# SP26_FindingTitan_Digital_Circuitry_Prak.net
KiCad netlist of a schematic drawn in Altium Designer
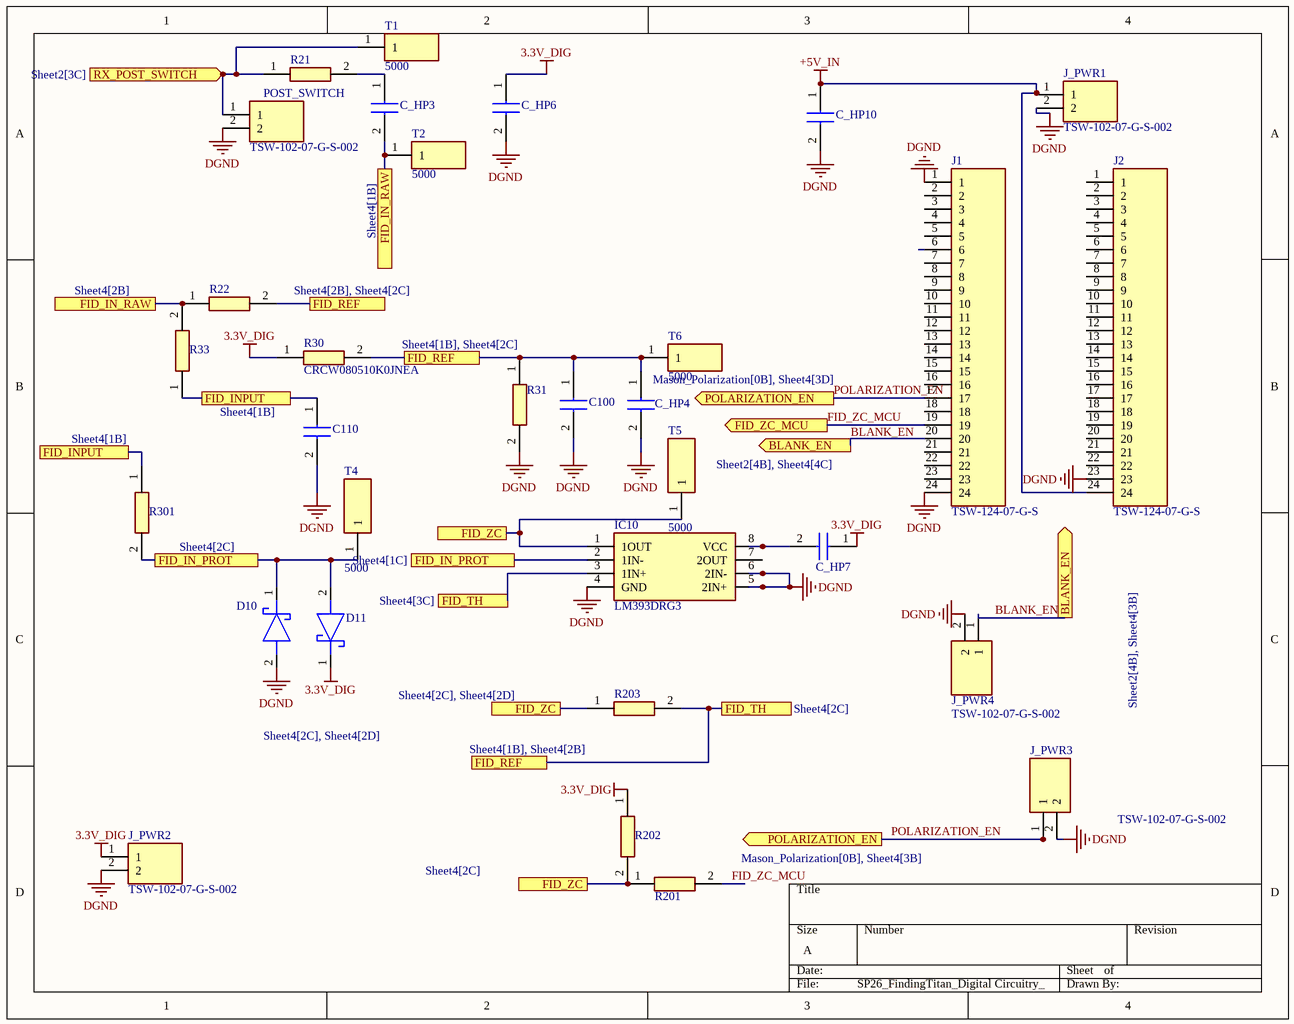
[diagram p0: SP26_FindingTitan_Digital Circuitry_Prakul Swaminath.SchDoc.SchDoc]

(export (version "E")
  (design (tool "Eeschema 10.0.6"))
  (components
    (comp (ref "C100")
      (value "C0805C105K5RACTU")
      (footprint "SamacSys:C0805")
      (description "Capacitor")
      (fields (field (name "MOUSER PART NUMBER") "80-C0805C105K5R"))
      (libsource (lib "*") (part "C0805C105K5RACTU"))
    )
    (comp (ref "C110")
      (value "GRM188R71H222KA01D")
      (footprint "SamacSys:CAPC1608X90N")
      (description "Capacitor")
      (fields (field (name "MOUSER PART NUMBER") "81-GRM39X222K50D"))
      (libsource (lib "*") (part "GRM188R71H222KA01D"))
    )
    (comp (ref "C_HP3")
      (value "C0603C104K5RACTU7042")
      (footprint "SamacSys:CAPC1608X95N")
      (description "Capacitor")
      (libsource (lib "*") (part "C0603C104K5RACTU7042"))
    )
    (comp (ref "C_HP4")
      (value "C0603C104K5RACTU7042C0603C104K5RACTU7042")
      (footprint "SamacSys:CAPC1608X95N")
      (description "Capacitor")
      (fields (field (name "MANUFACTURER_PART_NUMBER") "C0603C104K5RACTU7042"))
      (libsource (lib "*") (part "C0603C104K5RACTU7042"))
    )
    (comp (ref "C_HP6")
      (value "C0603C104K5RACTU7042C0603C104K5RACTU7042")
      (footprint "SamacSys:CAPC1608X95N")
      (description "Capacitor")
      (fields (field (name "MANUFACTURER_PART_NUMBER") "C0603C104K5RACTU7042"))
      (libsource (lib "*") (part "C0603C104K5RACTU7042"))
    )
    (comp (ref "C_HP7")
      (value "C0603C104K5RACTU7042C0603C104K5RACTU7042")
      (footprint "SamacSys:CAPC1608X95N")
      (description "Capacitor")
      (fields (field (name "MANUFACTURER_PART_NUMBER") "C0603C104K5RACTU7042"))
      (libsource (lib "*") (part "C0603C104K5RACTU7042"))
    )
    (comp (ref "C_HP10")
      (value "C0603C104K5RACTU7042C0603C104K5RACTU7042")
      (footprint "SamacSys:CAPC1608X95N")
      (description "Capacitor")
      (fields (field (name "MANUFACTURER_PART_NUMBER") "C0603C104K5RACTU7042"))
      (libsource (lib "*") (part "C0603C104K5RACTU7042"))
    )
    (comp (ref "D10")
      (value "BAT54HT1G")
      (footprint "SamacSys:SOD2512X110N")
      (description "Schottky Diode")
      (fields (field (name "MOUSER PART NUMBER") "863-BAT54HT1G"))
      (libsource (lib "*") (part "BAT54HT1G"))
    )
    (comp (ref "D11")
      (value "BAT54HT1G")
      (footprint "SamacSys:SOD2512X110N")
      (description "Schottky Diode")
      (fields (field (name "MOUSER PART NUMBER") "863-BAT54HT1G"))
      (libsource (lib "*") (part "BAT54HT1G"))
    )
    (comp (ref "IC10")
      (value "LM393DRG3")
      (footprint "SamacSys:SOIC127P600X175-8N")
      (description "Integrated Circuit")
      (fields (field (name "MOUSER PART NUMBER") "595-LM393DRG3"))
      (libsource (lib "*") (part "LM393DRG3"))
    )
    (comp (ref "J1")
      (value "TSW-124-07-G-S")
      (footprint "SamacSys:TSW-124-XX-YY-S")
      (description "Connector")
      (fields (field (name "MOUSER PART NUMBER") "200-TSW12407GS"))
      (libsource (lib "*") (part "TSW-124-07-G-S"))
    )
    (comp (ref "J2")
      (value "TSW-124-07-G-S")
      (footprint "SamacSys:TSW-124-XX-YY-S")
      (description "Connector")
      (fields (field (name "MOUSER PART NUMBER") "200-TSW12407GS"))
      (libsource (lib "*") (part "TSW-124-07-G-S"))
    )
    (comp (ref "J_PWR1")
      (value "TSW-102-07-G-S-002")
      (footprint "SamacSys:HDRV2W64P0X254_1X2_508X254X838P")
      (description "Connector")
      (fields (field (name "MOUSER PART NUMBER") "200-TSW-10207GS002"))
      (libsource (lib "*") (part "TSW-102-07-G-S-002"))
    )
    (comp (ref "J_PWR2")
      (value "TSW-102-07-G-S-002")
      (footprint "SamacSys:HDRV2W64P0X254_1X2_508X254X838P")
      (description "Connector")
      (fields (field (name "MOUSER PART NUMBER") "200-TSW-10207GS002"))
      (libsource (lib "*") (part "TSW-102-07-G-S-002"))
    )
    (comp (ref "J_PWR3")
      (value "TSW-102-07-G-S-002")
      (footprint "SamacSys:HDRV2W64P0X254_1X2_508X254X838P")
      (description "Connector")
      (fields (field (name "MOUSER PART NUMBER") "200-TSW-10207GS002"))
      (libsource (lib "") (part "TSW-102-07-G-S-002_2"))
    )
    (comp (ref "J_PWR4")
      (value "TSW-102-07-G-S-002")
      (footprint "SamacSys:HDRV2W64P0X254_1X2_508X254X838P")
      (description "Connector")
      (fields (field (name "MOUSER PART NUMBER") "200-TSW-10207GS002"))
      (libsource (lib "") (part "TSW-102-07-G-S-002_1"))
    )
    (comp (ref "POST_SWITCH")
      (value "TSW-102-07-G-S-002")
      (footprint "SamacSys:HDRV2W64P0X254_1X2_508X254X838P")
      (description "Connector")
      (fields (field (name "MOUSER PART NUMBER") "200-TSW-10207GS002"))
      (libsource (lib "*") (part "TSW-102-07-G-S-002"))
    )
    (comp (ref "R21")
      (value "RMCF0603FT1K00")
      (footprint "SamacSys:RESC1608X55N")
      (description "Resistor")
      (fields (field (name "MOUSER PART NUMBER") "708-RMCF0603FT1K00"))
      (libsource (lib "*") (part "RMCF0603FT1K00"))
    )
    (comp (ref "R22")
      (value "RC0805FR-07100KL")
      (footprint "SamacSys:RESC2012X60N")
      (description "Resistor")
      (fields (field (name "MOUSER PART NUMBER") "603-RC0805FR-07100KL"))
      (libsource (lib "*") (part "RC0805FR-07100KL"))
    )
    (comp (ref "R30")
      (value "CRCW080510K0JNEA")
      (footprint "SamacSys:RESC2012X50N")
      (description "Resistor")
      (fields (field (name "MOUSER PART NUMBER") "71-CRCW0805J-10K-E3"))
      (libsource (lib "") (part "CRCW080510K0JNEA_1"))
    )
    (comp (ref "R31")
      (value "CRCW080510K0JNEA")
      (footprint "SamacSys:RESC2012X50N")
      (description "Resistor")
      (fields (field (name "MOUSER PART NUMBER") "71-CRCW0805J-10K-E3"))
      (libsource (lib "*") (part "CRCW080510K0JNEA"))
    )
    (comp (ref "R33")
      (value "RC0402JR-074K7L")
      (footprint "SamacSys:RESC2012X60N")
      (description "Resistor")
      (fields
        (field (name "MANUFACTURER_PART_NUMBER") "RC0805FR-07100KL")
        (field (name "MOUSER PART NUMBER") "603-RC0805FR-07100KL")
      )
      (libsource (lib "") (part "RC0805FR-07100KL_1"))
    )
    (comp (ref "R201")
      (value "CRCW080547R0FKEA")
      (footprint "SamacSys:RESC2012X60N")
      (description "Resistor")
      (fields
        (field (name "MANUFACTURER_PART_NUMBER") "CRCW080510K0FKEAHP")
        (field (name "MOUSER PART NUMBER") "71-CRCW080510K0FKEAH")
      )
      (libsource (lib "*") (part "CRCW080510K0FKEAHP"))
    )
    (comp (ref "R202")
      (value "CRCW08054K70FKEA")
      (footprint "SamacSys:RESC2012X60N")
      (description "Resistor")
      (fields
        (field (name "MANUFACTURER_PART_NUMBER") "CRCW080510K0FKEAHP")
        (field (name "MOUSER PART NUMBER") "71-CRCW080510K0FKEAH")
      )
      (libsource (lib "") (part "CRCW080510K0FKEAHP_1"))
    )
    (comp (ref "R203")
      (value "CRCW08051M00FKEAHP")
      (footprint "SamacSys:RESC2012X60N")
      (description "Resistor")
      (fields (field (name "MOUSER PART NUMBER") "71-CRCW08051M00FKEAH"))
      (libsource (lib "*") (part "CRCW08051M00FKEAHP"))
    )
    (comp (ref "R301")
      (value "RC0805FR-07220RL")
      (footprint "SamacSys:RESC2012X60N")
      (description "Resistor")
      (fields (field (name "MOUSER PART NUMBER") "603-RC0805FR-07220RL"))
      (libsource (lib "*") (part "RC0805FR-07220RL"))
    )
    (comp (ref "T1")
      (value "5000")
      (footprint "SamacSys:5000")
      (description "Connector")
      (fields (field (name "MOUSER PART NUMBER") "534-5000"))
      (libsource (lib "") (part "5000_1"))
    )
    (comp (ref "T2")
      (value "5000")
      (footprint "SamacSys:5000")
      (description "Connector")
      (fields (field (name "MOUSER PART NUMBER") "534-5000"))
      (libsource (lib "") (part "5000_1"))
    )
    (comp (ref "T4")
      (value "5000")
      (footprint "SamacSys:5000")
      (description "Connector")
      (fields (field (name "MOUSER PART NUMBER") "534-5000"))
      (libsource (lib "*") (part "5000"))
    )
    (comp (ref "T5")
      (value "5000")
      (footprint "SamacSys:5000")
      (description "Connector")
      (fields (field (name "MOUSER PART NUMBER") "534-5000"))
      (libsource (lib "*") (part "5000"))
    )
    (comp (ref "T6")
      (value "5000")
      (footprint "SamacSys:5000")
      (description "Connector")
      (fields (field (name "MOUSER PART NUMBER") "534-5000"))
      (libsource (lib "") (part "5000_1"))
    )
  )
  (nets
    (net (code "1") (name "+5V_IN") (class "Default")
      (node (ref "C_HP10") (pin "1") (pinfunction "1_1") (pintype "passive"))
      (node (ref "J2") (pin "24") (pinfunction "24_24") (pintype "passive"))
      (node (ref "J_PWR1") (pin "1") (pinfunction "1_1") (pintype "passive"))
    )
    (net (code "3") (name "/BLANK_EN") (class "Default")
      (node (ref "J1") (pin "20") (pinfunction "20_20") (pintype "passive"))
      (node (ref "J_PWR4") (pin "1") (pinfunction "1_1") (pintype "passive"))
    )
    (net (code "4") (name "/FID_INPUT") (class "Default")
      (node (ref "C110") (pin "1") (pinfunction "1_1") (pintype "passive"))
      (node (ref "R301") (pin "1") (pinfunction "1_1") (pintype "passive"))
      (node (ref "R33") (pin "1") (pinfunction "1_1") (pintype "passive"))
    )
    (net (code "5") (name "/FID_IN_PROT") (class "Default")
      (node (ref "D10") (pin "1") (pinfunction "K_1") (pintype "passive"))
      (node (ref "D11") (pin "2") (pinfunction "A_2") (pintype "passive"))
      (node (ref "IC10") (pin "2") (pinfunction "1IN-_2") (pintype "passive"))
      (node (ref "R301") (pin "2") (pinfunction "2_2") (pintype "passive"))
      (node (ref "T4") (pin "1") (pinfunction "1_1") (pintype "passive"))
    )
    (net (code "6") (name "/FID_IN_RAW") (class "Default")
      (node (ref "C_HP3") (pin "2") (pinfunction "2_2") (pintype "passive"))
      (node (ref "R22") (pin "1") (pinfunction "1_1") (pintype "passive"))
      (node (ref "R33") (pin "2") (pinfunction "2_2") (pintype "passive"))
      (node (ref "T2") (pin "1") (pinfunction "1_1") (pintype "passive"))
    )
    (net (code "7") (name "/FID_REF") (class "Default")
      (node (ref "C100") (pin "1") (pinfunction "1_1") (pintype "passive"))
      (node (ref "C_HP4") (pin "1") (pinfunction "1_1") (pintype "passive"))
      (node (ref "IC10") (pin "3") (pinfunction "1IN+_3") (pintype "passive"))
      (node (ref "R203") (pin "2") (pinfunction "2_2") (pintype "passive"))
      (node (ref "R22") (pin "2") (pinfunction "2_2") (pintype "passive"))
      (node (ref "R30") (pin "2") (pinfunction "2_2") (pintype "passive"))
      (node (ref "R31") (pin "1") (pinfunction "1_1") (pintype "passive"))
      (node (ref "T6") (pin "1") (pinfunction "1_1") (pintype "passive"))
    )
    (net (code "8") (name "/FID_ZC") (class "Default")
      (node (ref "IC10") (pin "1") (pinfunction "1OUT_1") (pintype "passive"))
      (node (ref "R201") (pin "1") (pinfunction "1_1") (pintype "passive"))
      (node (ref "R202") (pin "2") (pinfunction "2_2") (pintype "passive"))
      (node (ref "R203") (pin "1") (pinfunction "1_1") (pintype "passive"))
      (node (ref "T5") (pin "1") (pinfunction "1_1") (pintype "passive"))
    )
    (net (code "9") (name "/FID_ZC_MCU") (class "Default")
      (node (ref "J1") (pin "19") (pinfunction "19_19") (pintype "passive"))
      (node (ref "R201") (pin "2") (pinfunction "2_2") (pintype "passive"))
    )
    (net (code "10") (name "/POLARIZATION_EN") (class "Default")
      (node (ref "J1") (pin "17") (pinfunction "17_17") (pintype "passive"))
      (node (ref "J_PWR3") (pin "1") (pinfunction "1_1") (pintype "passive"))
    )
    (net (code "11") (name "/RX_POST_SWITCH") (class "Default")
      (node (ref "POST_SWITCH") (pin "1") (pinfunction "1_1") (pintype "passive"))
      (node (ref "R21") (pin "1") (pinfunction "1_1") (pintype "passive"))
      (node (ref "T1") (pin "1") (pinfunction "1_1") (pintype "passive"))
    )
    (net (code "12") (name "3.3V_DIG") (class "Default")
      (node (ref "C_HP6") (pin "1") (pinfunction "1_1") (pintype "passive"))
      (node (ref "C_HP7") (pin "1") (pinfunction "1_1") (pintype "passive"))
      (node (ref "D11") (pin "1") (pinfunction "K_1") (pintype "passive"))
      (node (ref "J_PWR2") (pin "1") (pinfunction "1_1") (pintype "passive"))
      (node (ref "R202") (pin "1") (pinfunction "1_1") (pintype "passive"))
      (node (ref "R30") (pin "1") (pinfunction "1_1") (pintype "passive"))
    )
    (net (code "13") (name "DGND") (class "Default")
      (node (ref "C100") (pin "2") (pinfunction "2_2") (pintype "passive"))
      (node (ref "C110") (pin "2") (pinfunction "2_2") (pintype "passive"))
      (node (ref "C_HP10") (pin "2") (pinfunction "2_2") (pintype "passive"))
      (node (ref "C_HP4") (pin "2") (pinfunction "2_2") (pintype "passive"))
      (node (ref "C_HP6") (pin "2") (pinfunction "2_2") (pintype "passive"))
      (node (ref "D10") (pin "2") (pinfunction "A_2") (pintype "passive"))
      (node (ref "IC10") (pin "4") (pinfunction "GND_4") (pintype "passive"))
      (node (ref "IC10") (pin "5") (pinfunction "2IN+_5") (pintype "passive"))
      (node (ref "IC10") (pin "6") (pinfunction "2IN-_6") (pintype "passive"))
      (node (ref "J1") (pin "1") (pinfunction "1_1") (pintype "passive"))
      (node (ref "J1") (pin "24") (pinfunction "24_24") (pintype "passive"))
      (node (ref "J2") (pin "23") (pinfunction "23_23") (pintype "passive"))
      (node (ref "J_PWR1") (pin "2") (pinfunction "2_2") (pintype "passive"))
      (node (ref "J_PWR2") (pin "2") (pinfunction "2_2") (pintype "passive"))
      (node (ref "J_PWR3") (pin "2") (pinfunction "2_2") (pintype "passive"))
      (node (ref "J_PWR4") (pin "2") (pinfunction "2_2") (pintype "passive"))
      (node (ref "POST_SWITCH") (pin "2") (pinfunction "2_2") (pintype "passive"))
      (node (ref "R31") (pin "2") (pinfunction "2_2") (pintype "passive"))
    )
    (net (code "14") (name "Net-(C_HP3-Pad1)") (class "Default")
      (node (ref "C_HP3") (pin "1") (pinfunction "1_1") (pintype "passive"))
      (node (ref "R21") (pin "2") (pinfunction "2_2") (pintype "passive"))
    )
    (net (code "15") (name "Net-(IC10-VCC)") (class "Default")
      (node (ref "C_HP7") (pin "2") (pinfunction "2_2") (pintype "passive"))
      (node (ref "IC10") (pin "8") (pinfunction "VCC_8") (pintype "passive"))
    )
    (net (code "16") (name "unconnected-(IC10-2OUT-Pad7)") (class "Default")
      (node (ref "IC10") (pin "7") (pinfunction "2OUT_7") (pintype "passive"))
    )
    (net (code "17") (name "unconnected-(J1-Pad2)") (class "Default")
      (node (ref "J1") (pin "2") (pinfunction "2_2") (pintype "passive"))
    )
    (net (code "18") (name "unconnected-(J1-Pad3)") (class "Default")
      (node (ref "J1") (pin "3") (pinfunction "3_3") (pintype "passive"))
    )
    (net (code "19") (name "unconnected-(J1-Pad4)") (class "Default")
      (node (ref "J1") (pin "4") (pinfunction "4_4") (pintype "passive"))
    )
    (net (code "20") (name "unconnected-(J1-Pad5)") (class "Default")
      (node (ref "J1") (pin "5") (pinfunction "5_5") (pintype "passive"))
    )
    (net (code "21") (name "unconnected-(J1-Pad6)") (class "Default")
      (node (ref "J1") (pin "6") (pinfunction "6_6") (pintype "passive"))
    )
    (net (code "22") (name "unconnected-(J1-Pad7)") (class "Default")
      (node (ref "J1") (pin "7") (pinfunction "7_7") (pintype "passive"))
    )
    (net (code "23") (name "unconnected-(J1-Pad8)") (class "Default")
      (node (ref "J1") (pin "8") (pinfunction "8_8") (pintype "passive"))
    )
    (net (code "24") (name "unconnected-(J1-Pad9)") (class "Default")
      (node (ref "J1") (pin "9") (pinfunction "9_9") (pintype "passive"))
    )
    (net (code "25") (name "unconnected-(J1-Pad10)") (class "Default")
      (node (ref "J1") (pin "10") (pinfunction "10_10") (pintype "passive"))
    )
    (net (code "26") (name "unconnected-(J1-Pad11)") (class "Default")
      (node (ref "J1") (pin "11") (pinfunction "11_11") (pintype "passive"))
    )
    (net (code "27") (name "unconnected-(J1-Pad12)") (class "Default")
      (node (ref "J1") (pin "12") (pinfunction "12_12") (pintype "passive"))
    )
    (net (code "28") (name "unconnected-(J1-Pad13)") (class "Default")
      (node (ref "J1") (pin "13") (pinfunction "13_13") (pintype "passive"))
    )
    (net (code "29") (name "unconnected-(J1-Pad14)") (class "Default")
      (node (ref "J1") (pin "14") (pinfunction "14_14") (pintype "passive"))
    )
    (net (code "30") (name "unconnected-(J1-Pad15)") (class "Default")
      (node (ref "J1") (pin "15") (pinfunction "15_15") (pintype "passive"))
    )
    (net (code "31") (name "unconnected-(J1-Pad16)") (class "Default")
      (node (ref "J1") (pin "16") (pinfunction "16_16") (pintype "passive"))
    )
    (net (code "32") (name "unconnected-(J1-Pad18)") (class "Default")
      (node (ref "J1") (pin "18") (pinfunction "18_18") (pintype "passive"))
    )
    (net (code "33") (name "unconnected-(J1-Pad21)") (class "Default")
      (node (ref "J1") (pin "21") (pinfunction "21_21") (pintype "passive"))
    )
    (net (code "34") (name "unconnected-(J1-Pad22)") (class "Default")
      (node (ref "J1") (pin "22") (pinfunction "22_22") (pintype "passive"))
    )
    (net (code "35") (name "unconnected-(J1-Pad23)") (class "Default")
      (node (ref "J1") (pin "23") (pinfunction "23_23") (pintype "passive"))
    )
    (net (code "36") (name "unconnected-(J2-Pad1)") (class "Default")
      (node (ref "J2") (pin "1") (pinfunction "1_1") (pintype "passive"))
    )
    (net (code "37") (name "unconnected-(J2-Pad2)") (class "Default")
      (node (ref "J2") (pin "2") (pinfunction "2_2") (pintype "passive"))
    )
    (net (code "38") (name "unconnected-(J2-Pad3)") (class "Default")
      (node (ref "J2") (pin "3") (pinfunction "3_3") (pintype "passive"))
    )
    (net (code "39") (name "unconnected-(J2-Pad4)") (class "Default")
      (node (ref "J2") (pin "4") (pinfunction "4_4") (pintype "passive"))
    )
    (net (code "40") (name "unconnected-(J2-Pad5)") (class "Default")
      (node (ref "J2") (pin "5") (pinfunction "5_5") (pintype "passive"))
    )
    (net (code "41") (name "unconnected-(J2-Pad6)") (class "Default")
      (node (ref "J2") (pin "6") (pinfunction "6_6") (pintype "passive"))
    )
    (net (code "42") (name "unconnected-(J2-Pad7)") (class "Default")
      (node (ref "J2") (pin "7") (pinfunction "7_7") (pintype "passive"))
    )
    (net (code "43") (name "unconnected-(J2-Pad8)") (class "Default")
      (node (ref "J2") (pin "8") (pinfunction "8_8") (pintype "passive"))
    )
    (net (code "44") (name "unconnected-(J2-Pad9)") (class "Default")
      (node (ref "J2") (pin "9") (pinfunction "9_9") (pintype "passive"))
    )
    (net (code "45") (name "unconnected-(J2-Pad10)") (class "Default")
      (node (ref "J2") (pin "10") (pinfunction "10_10") (pintype "passive"))
    )
    (net (code "46") (name "unconnected-(J2-Pad11)") (class "Default")
      (node (ref "J2") (pin "11") (pinfunction "11_11") (pintype "passive"))
    )
    (net (code "47") (name "unconnected-(J2-Pad12)") (class "Default")
      (node (ref "J2") (pin "12") (pinfunction "12_12") (pintype "passive"))
    )
    (net (code "48") (name "unconnected-(J2-Pad13)") (class "Default")
      (node (ref "J2") (pin "13") (pinfunction "13_13") (pintype "passive"))
    )
    (net (code "49") (name "unconnected-(J2-Pad14)") (class "Default")
      (node (ref "J2") (pin "14") (pinfunction "14_14") (pintype "passive"))
    )
    (net (code "50") (name "unconnected-(J2-Pad15)") (class "Default")
      (node (ref "J2") (pin "15") (pinfunction "15_15") (pintype "passive"))
    )
    (net (code "51") (name "unconnected-(J2-Pad16)") (class "Default")
      (node (ref "J2") (pin "16") (pinfunction "16_16") (pintype "passive"))
    )
    (net (code "52") (name "unconnected-(J2-Pad17)") (class "Default")
      (node (ref "J2") (pin "17") (pinfunction "17_17") (pintype "passive"))
    )
    (net (code "53") (name "unconnected-(J2-Pad18)") (class "Default")
      (node (ref "J2") (pin "18") (pinfunction "18_18") (pintype "passive"))
    )
    (net (code "54") (name "unconnected-(J2-Pad19)") (class "Default")
      (node (ref "J2") (pin "19") (pinfunction "19_19") (pintype "passive"))
    )
    (net (code "55") (name "unconnected-(J2-Pad20)") (class "Default")
      (node (ref "J2") (pin "20") (pinfunction "20_20") (pintype "passive"))
    )
    (net (code "56") (name "unconnected-(J2-Pad21)") (class "Default")
      (node (ref "J2") (pin "21") (pinfunction "21_21") (pintype "passive"))
    )
    (net (code "57") (name "unconnected-(J2-Pad22)") (class "Default")
      (node (ref "J2") (pin "22") (pinfunction "22_22") (pintype "passive"))
    )
  )
)
